# connectors_and_mosfets.net
KiCad netlist of a schematic drawn in Altium Designer
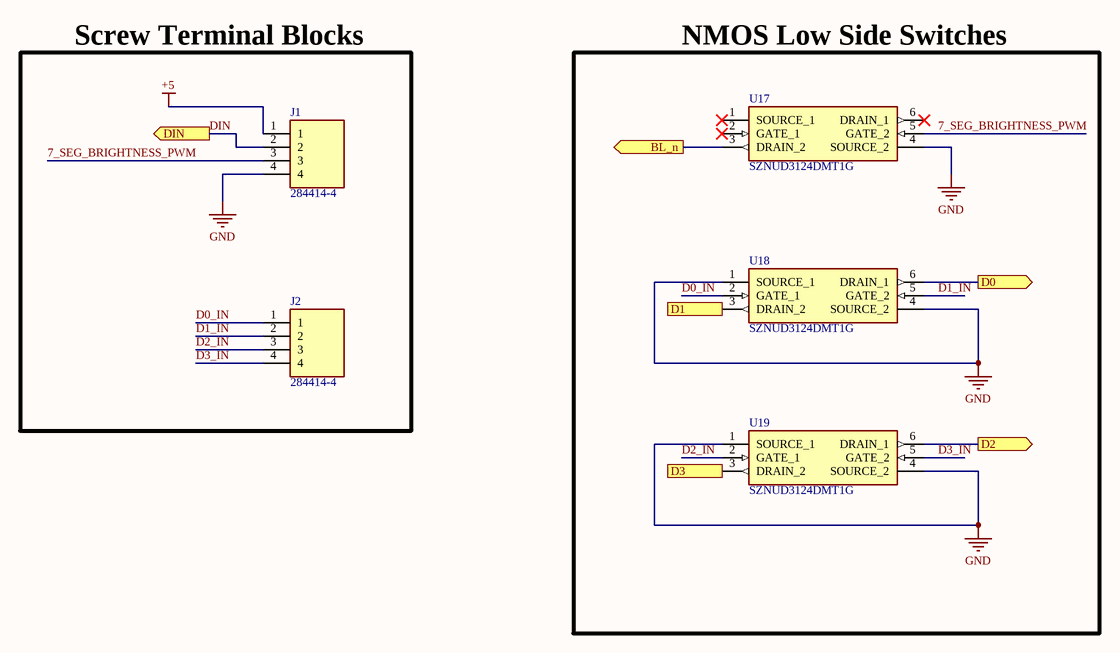
[diagram p0: connectors_and_mosfets.SchDoc]

(export (version "E")
  (design (tool "Eeschema 10.0.6"))
  (components
    (comp (ref "J1")
      (value "284414-4")
      (footprint "SamacSys:2844144")
      (description "Connector")
      (fields (field (name "MOUSER PART NUMBER") "571-284414-4"))
      (libsource (lib "*") (part "284414-4"))
    )
    (comp (ref "J2")
      (value "284414-4")
      (footprint "SamacSys:2844144")
      (description "Connector")
      (fields (field (name "MOUSER PART NUMBER") "571-284414-4"))
      (libsource (lib "*") (part "284414-4"))
    )
    (comp (ref "U17")
      (value "SZNUD3124DMT1G")
      (footprint "SamacSys:SOT95P275X110-6N")
      (description "Integrated Circuit")
      (fields (field (name "MOUSER PART NUMBER") "863-SZNUD3124DMT1G"))
      (libsource (lib "*") (part "SZNUD3124DMT1G"))
    )
    (comp (ref "U18")
      (value "SZNUD3124DMT1G")
      (footprint "SamacSys:SOT95P275X110-6N")
      (description "Integrated Circuit")
      (fields (field (name "MOUSER PART NUMBER") "863-SZNUD3124DMT1G"))
      (libsource (lib "*") (part "SZNUD3124DMT1G"))
    )
    (comp (ref "U19")
      (value "SZNUD3124DMT1G")
      (footprint "SamacSys:SOT95P275X110-6N")
      (description "Integrated Circuit")
      (fields (field (name "MOUSER PART NUMBER") "863-SZNUD3124DMT1G"))
      (libsource (lib "*") (part "SZNUD3124DMT1G"))
    )
  )
  (nets
    (net (code "1") (name "+5") (class "Default")
      (node (ref "J1") (pin "1") (pinfunction "1_1") (pintype "passive"))
    )
    (net (code "2") (name "/7_SEG_BRIGHTNESS_PWM") (class "Default")
      (node (ref "J1") (pin "3") (pinfunction "3_3") (pintype "passive"))
      (node (ref "U17") (pin "5") (pinfunction "GATE_2_5") (pintype "input"))
    )
    (net (code "3") (name "/BL_n") (class "Default")
      (node (ref "U17") (pin "3") (pinfunction "DRAIN_2_3") (pintype "output"))
    )
    (net (code "4") (name "/D0") (class "Default")
      (node (ref "U18") (pin "6") (pinfunction "DRAIN_1_6") (pintype "output"))
    )
    (net (code "5") (name "/D0_IN") (class "Default")
      (node (ref "J2") (pin "1") (pinfunction "1_1") (pintype "passive"))
      (node (ref "U18") (pin "2") (pinfunction "GATE_1_2") (pintype "input"))
    )
    (net (code "6") (name "/D1") (class "Default")
      (node (ref "U18") (pin "3") (pinfunction "DRAIN_2_3") (pintype "output"))
    )
    (net (code "7") (name "/D1_IN") (class "Default")
      (node (ref "J2") (pin "2") (pinfunction "2_2") (pintype "passive"))
      (node (ref "U18") (pin "5") (pinfunction "GATE_2_5") (pintype "input"))
    )
    (net (code "8") (name "/D2") (class "Default")
      (node (ref "U19") (pin "6") (pinfunction "DRAIN_1_6") (pintype "output"))
    )
    (net (code "9") (name "/D2_IN") (class "Default")
      (node (ref "J2") (pin "3") (pinfunction "3_3") (pintype "passive"))
      (node (ref "U19") (pin "2") (pinfunction "GATE_1_2") (pintype "input"))
    )
    (net (code "10") (name "/D3") (class "Default")
      (node (ref "U19") (pin "3") (pinfunction "DRAIN_2_3") (pintype "output"))
    )
    (net (code "11") (name "/D3_IN") (class "Default")
      (node (ref "J2") (pin "4") (pinfunction "4_4") (pintype "passive"))
      (node (ref "U19") (pin "5") (pinfunction "GATE_2_5") (pintype "input"))
    )
    (net (code "12") (name "/DIN") (class "Default")
      (node (ref "J1") (pin "2") (pinfunction "2_2") (pintype "passive"))
    )
    (net (code "13") (name "GND") (class "Default")
      (node (ref "J1") (pin "4") (pinfunction "4_4") (pintype "passive"))
      (node (ref "U17") (pin "4") (pinfunction "SOURCE_2_4") (pintype "power_in"))
      (node (ref "U18") (pin "1") (pinfunction "SOURCE_1_1") (pintype "power_in"))
      (node (ref "U18") (pin "4") (pinfunction "SOURCE_2_4") (pintype "power_in"))
      (node (ref "U19") (pin "1") (pinfunction "SOURCE_1_1") (pintype "power_in"))
      (node (ref "U19") (pin "4") (pinfunction "SOURCE_2_4") (pintype "power_in"))
    )
    (net (code "14") (name "unconnected-(U17-DRAIN_1-Pad6)") (class "Default")
      (node (ref "U17") (pin "6") (pinfunction "DRAIN_1_6") (pintype "output+no_connect"))
    )
    (net (code "15") (name "unconnected-(U17-GATE_1-Pad2)") (class "Default")
      (node (ref "U17") (pin "2") (pinfunction "GATE_1_2") (pintype "input+no_connect"))
    )
    (net (code "16") (name "unconnected-(U17-SOURCE_1-Pad1)") (class "Default")
      (node (ref "U17") (pin "1") (pinfunction "SOURCE_1_1") (pintype "power_in+no_connect"))
    )
  )
)
